# FourRotor2_0.net
KiCad netlist of a schematic drawn in Altium Designer
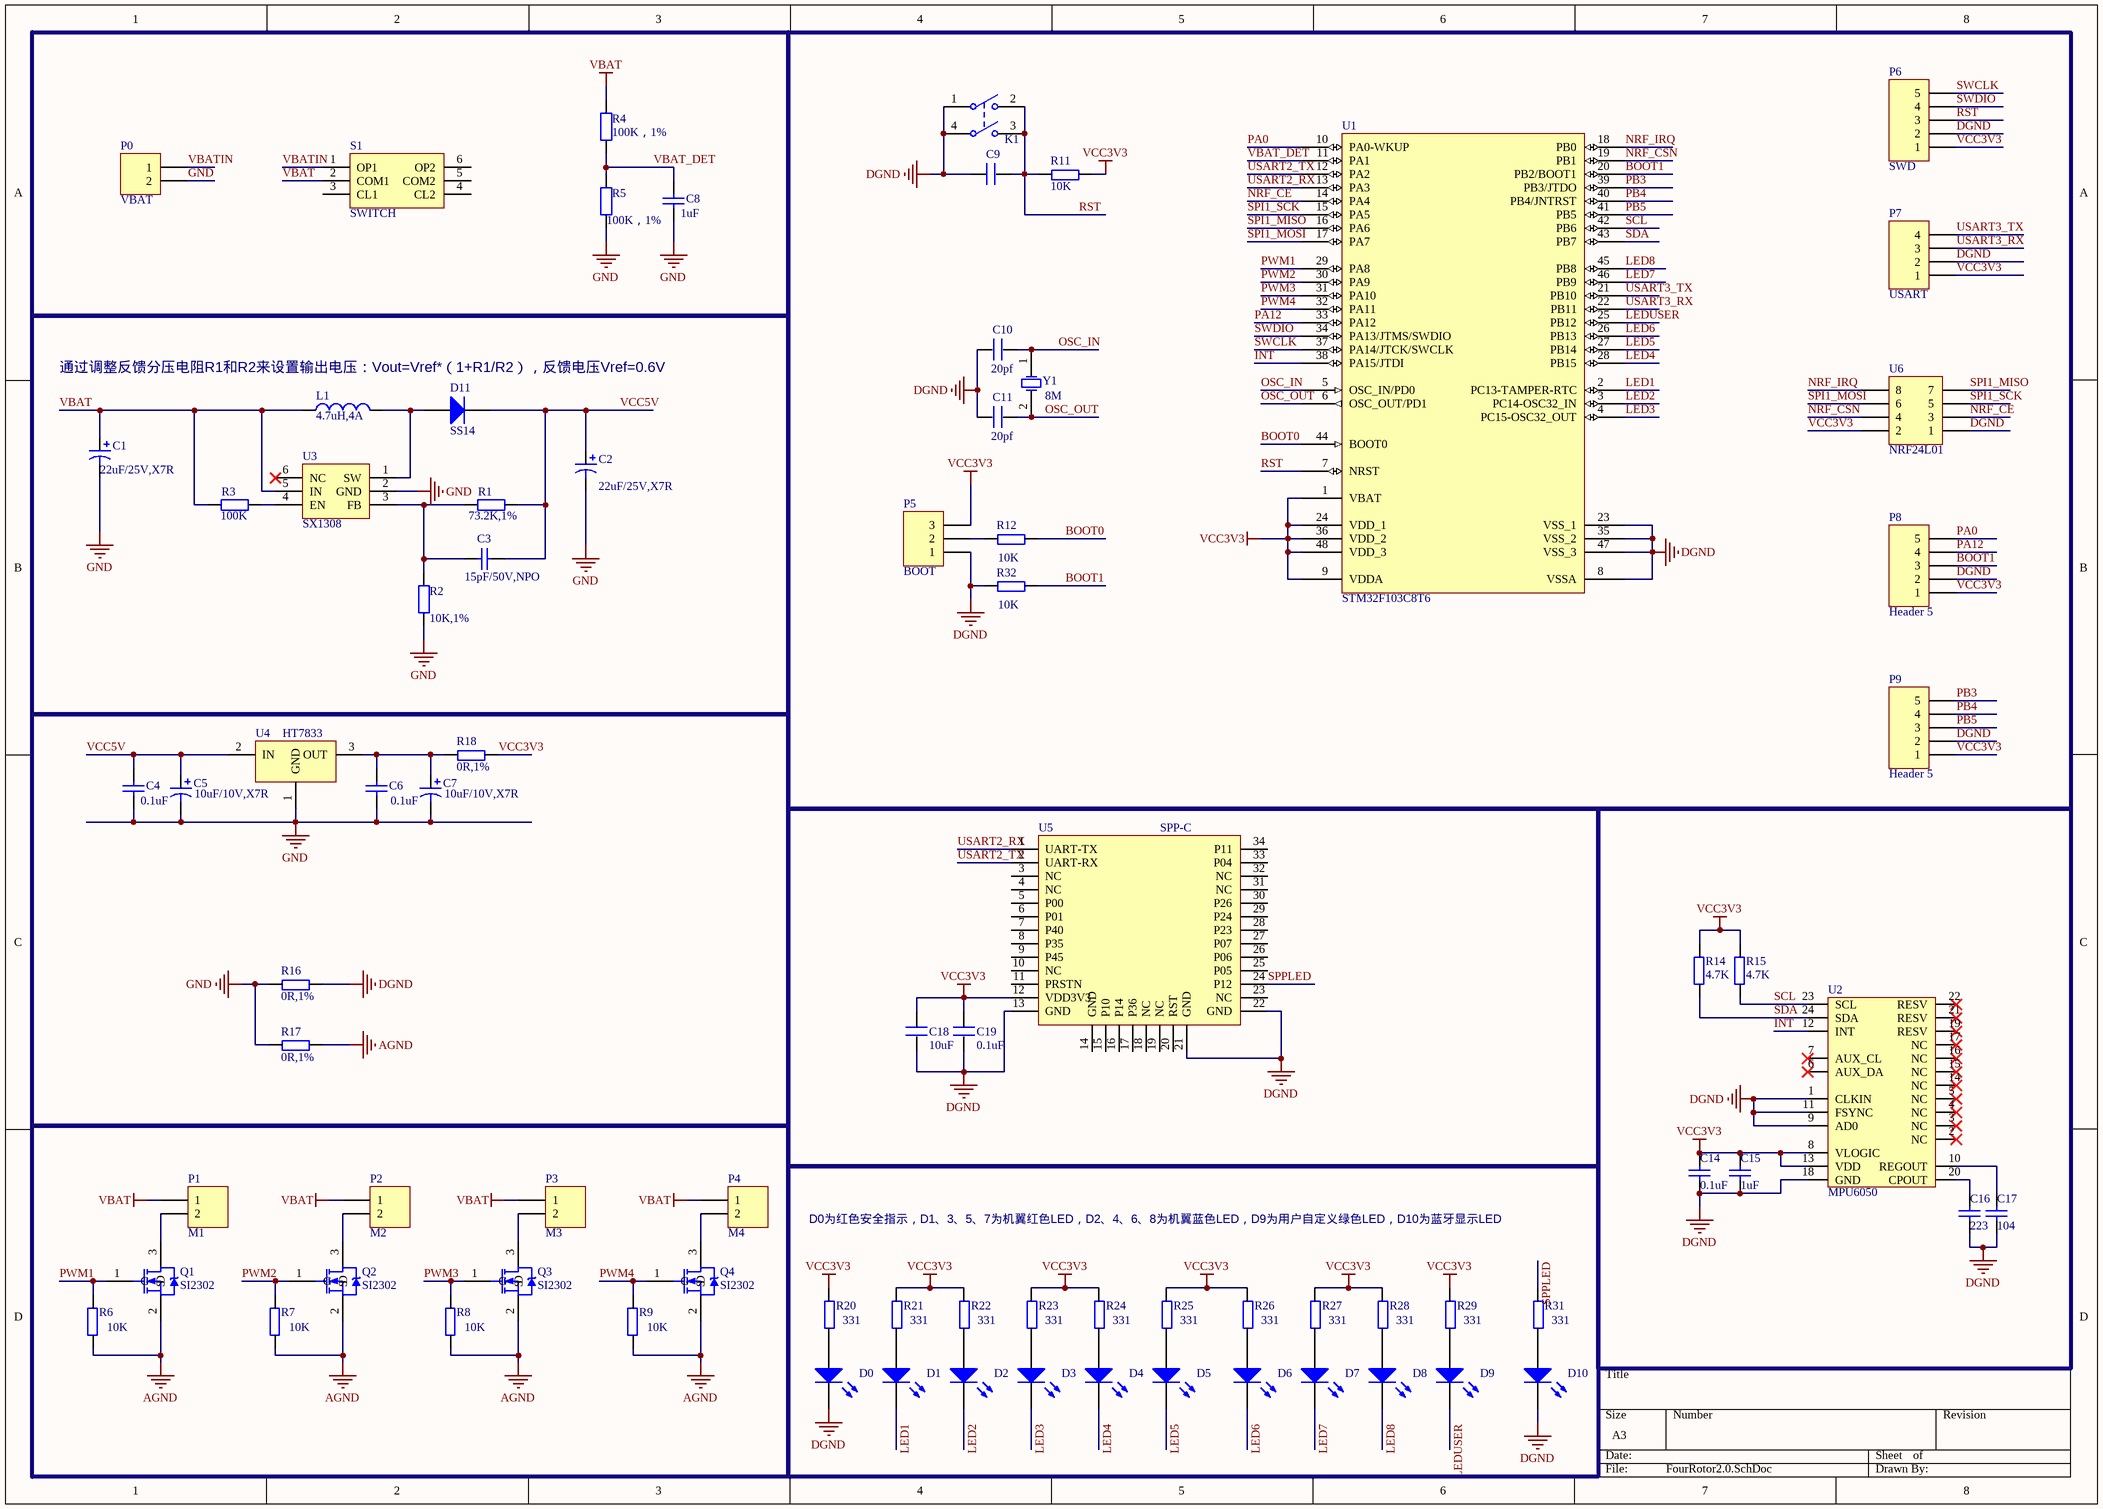
[diagram p0: FourRotor2.0.SchDoc]

(export (version "E")
  (design (tool "Eeschema 10.0.6"))
  (components
    (comp (ref "C1")
      (value "22uF/25V,X7R")
      (footprint "LC-1206_C")
      (description "Polarized Capacitor (Radial)")
      (fields (field (name "Comment") "Cap Pol1") (field (name "PUBLISHER") "Altium Limited"))
      (libsource (lib "Miscellaneous Devices") (part "Cap Pol1"))
    )
    (comp (ref "C2")
      (value "22uF/25V,X7R")
      (footprint "LC-1206_C")
      (description "Polarized Capacitor (Radial)")
      (fields (field (name "Comment") "Cap Pol1") (field (name "PUBLISHER") "Altium Limited"))
      (libsource (lib "Miscellaneous Devices") (part "Cap Pol1"))
    )
    (comp (ref "C3")
      (value "15pF/50V,NPO")
      (footprint "LC-0603_C")
      (description "Capacitor")
      (fields (field (name "Comment") "Cap") (field (name "PUBLISHER") "Altium Limited"))
      (libsource (lib "Miscellaneous Devices") (part "Cap"))
    )
    (comp (ref "C4")
      (value "0.1uF")
      (footprint "LC-0603_C")
      (description "Capacitor")
      (fields (field (name "Comment") "Cap") (field (name "PUBLISHER") "Altium Limited"))
      (libsource (lib "Miscellaneous Devices") (part "Cap"))
    )
    (comp (ref "C5")
      (value "10uF/10V,X7R")
      (footprint "LC-1206_C")
      (description "Polarized Capacitor (Radial)")
      (fields (field (name "Comment") "Cap Pol1") (field (name "PUBLISHER") "Altium Limited"))
      (libsource (lib "Miscellaneous Devices") (part "Cap Pol1"))
    )
    (comp (ref "C6")
      (value "0.1uF")
      (footprint "LC-0603_C")
      (description "Capacitor")
      (fields (field (name "Comment") "Cap") (field (name "PUBLISHER") "Altium Limited"))
      (libsource (lib "Miscellaneous Devices") (part "Cap"))
    )
    (comp (ref "C7")
      (value "10uF/10V,X7R")
      (footprint "LC-1206_C")
      (description "Polarized Capacitor (Radial)")
      (fields (field (name "Comment") "Cap Pol1") (field (name "PUBLISHER") "Altium Limited"))
      (libsource (lib "Miscellaneous Devices") (part "Cap Pol1"))
    )
    (comp (ref "C8")
      (value "1uF")
      (footprint "LC-0603_C")
      (description "Capacitor")
      (fields (field (name "Comment") "Cap") (field (name "PUBLISHER") "Altium Limited"))
      (libsource (lib "Miscellaneous Devices") (part "Cap"))
    )
    (comp (ref "C9")
      (value "1uF")
      (footprint "LC-0603_C")
      (libsource (lib "Explorer STM32F407封装库") (part "C_1"))
    )
    (comp (ref "C10")
      (value "20pf")
      (footprint "LC-0603_C")
      (libsource (lib "Explorer STM32F407封装库") (part "C"))
    )
    (comp (ref "C11")
      (value "20pf")
      (footprint "LC-0603_C")
      (libsource (lib "Explorer STM32F407封装库") (part "C"))
    )
    (comp (ref "C14")
      (value "0.1uF")
      (footprint "LC-0603_C")
      (description "Capacitor")
      (fields (field (name "PUBLISHER") "Altium Limited"))
      (libsource (lib "Miscellaneous Devices") (part "Cap"))
    )
    (comp (ref "C15")
      (value "1uF")
      (footprint "LC-0603_C")
      (description "Capacitor")
      (fields (field (name "PUBLISHER") "Altium Limited"))
      (libsource (lib "Miscellaneous Devices") (part "Cap"))
    )
    (comp (ref "C16")
      (value "223")
      (footprint "LC-0603_C")
      (description "Capacitor")
      (fields (field (name "PUBLISHER") "Altium Limited"))
      (libsource (lib "Miscellaneous Devices") (part "Cap"))
    )
    (comp (ref "C17")
      (value "104")
      (footprint "LC-0603_C")
      (description "Capacitor")
      (fields (field (name "PUBLISHER") "Altium Limited"))
      (libsource (lib "Miscellaneous Devices") (part "Cap"))
    )
    (comp (ref "C18")
      (value "10uF")
      (footprint "LC-0805_C")
      (libsource (lib "Explorer STM32F407封装库") (part "C"))
    )
    (comp (ref "C19")
      (value "0.1uF")
      (footprint "LC-0603_C")
      (libsource (lib "Explorer STM32F407封装库") (part "C"))
    )
    (comp (ref "D0")
      (value "LED0")
      (footprint "LC-0805_LED_S1")
      (description "Typical INFRARED GaAs LED")
      (fields (field (name "PUBLISHER") "Altium Limited"))
      (libsource (lib "Miscellaneous Devices") (part "LED0"))
    )
    (comp (ref "D1")
      (value "LED0")
      (footprint "LC-0805_LED_S1")
      (description "Typical INFRARED GaAs LED")
      (fields (field (name "PUBLISHER") "Altium Limited"))
      (libsource (lib "Miscellaneous Devices") (part "LED0"))
    )
    (comp (ref "D2")
      (value "LED0")
      (footprint "LC-0805_LED_S1")
      (description "Typical INFRARED GaAs LED")
      (fields (field (name "PUBLISHER") "Altium Limited"))
      (libsource (lib "Miscellaneous Devices") (part "LED0"))
    )
    (comp (ref "D3")
      (value "LED0")
      (footprint "LC-0805_LED_S1")
      (description "Typical INFRARED GaAs LED")
      (fields (field (name "PUBLISHER") "Altium Limited"))
      (libsource (lib "Miscellaneous Devices") (part "LED0"))
    )
    (comp (ref "D4")
      (value "LED0")
      (footprint "LC-0805_LED_S1")
      (description "Typical INFRARED GaAs LED")
      (fields (field (name "PUBLISHER") "Altium Limited"))
      (libsource (lib "Miscellaneous Devices") (part "LED0"))
    )
    (comp (ref "D5")
      (value "LED0")
      (footprint "LC-0805_LED_S1")
      (description "Typical INFRARED GaAs LED")
      (fields (field (name "PUBLISHER") "Altium Limited"))
      (libsource (lib "Miscellaneous Devices") (part "LED0"))
    )
    (comp (ref "D6")
      (value "LED0")
      (footprint "LC-0805_LED_S1")
      (description "Typical INFRARED GaAs LED")
      (fields (field (name "PUBLISHER") "Altium Limited"))
      (libsource (lib "Miscellaneous Devices") (part "LED0"))
    )
    (comp (ref "D7")
      (value "LED0")
      (footprint "LC-0805_LED_S1")
      (description "Typical INFRARED GaAs LED")
      (fields (field (name "PUBLISHER") "Altium Limited"))
      (libsource (lib "Miscellaneous Devices") (part "LED0"))
    )
    (comp (ref "D8")
      (value "LED0")
      (footprint "LC-0805_LED_S1")
      (description "Typical INFRARED GaAs LED")
      (fields (field (name "PUBLISHER") "Altium Limited"))
      (libsource (lib "Miscellaneous Devices") (part "LED0"))
    )
    (comp (ref "D9")
      (value "LED0")
      (footprint "LC-0805_LED_S1")
      (description "Typical INFRARED GaAs LED")
      (fields (field (name "PUBLISHER") "Altium Limited"))
      (libsource (lib "Miscellaneous Devices") (part "LED0"))
    )
    (comp (ref "D10")
      (value "LED0")
      (footprint "LC-0805_LED_S1")
      (description "Typical INFRARED GaAs LED")
      (fields (field (name "PUBLISHER") "Altium Limited"))
      (libsource (lib "Miscellaneous Devices") (part "LED0"))
    )
    (comp (ref "D11")
      (value "SS14")
      (footprint "LC-DO-214AC")
      (description "1 Amp General Purpose Rectifier")
      (fields (field (name "PUBLISHER") "Altium Limited"))
      (libsource (lib "Miscellaneous Devices") (part "Diode 1N4001"))
    )
    (comp (ref "K1")
      (value "SW-DPST")
      (footprint "SWITCH2")
      (description "Double-Pole, Single-Throw Switch")
      (fields (field (name "PUBLISHER") "Altium Limited"))
      (libsource (lib "Miscellaneous Devices") (part "SW-DPST"))
    )
    (comp (ref "L1")
      (value "4.7uH,4A")
      (footprint "LC-1812_L")
      (description "Inductor")
      (fields (field (name "PUBLISHER") "Altium Limited"))
      (libsource (lib "Miscellaneous Devices") (part "Inductor"))
    )
    (comp (ref "P0")
      (value "VBAT")
      (footprint "HDR1X2")
      (description "Header, 2-Pin")
      (fields (field (name "PUBLISHER") "Altium Limited"))
      (libsource (lib "") (part "Header 2_1"))
    )
    (comp (ref "P1")
      (value "M1")
      (footprint "HDR1X2")
      (description "Header, 2-Pin")
      (fields (field (name "PUBLISHER") "Altium Limited"))
      (libsource (lib "Miscellaneous Connectors") (part "Header 2"))
    )
    (comp (ref "P2")
      (value "M2")
      (footprint "HDR1X2")
      (description "Header, 2-Pin")
      (fields (field (name "PUBLISHER") "Altium Limited"))
      (libsource (lib "Miscellaneous Connectors") (part "Header 2"))
    )
    (comp (ref "P3")
      (value "M3")
      (footprint "HDR1X2")
      (description "Header, 2-Pin")
      (fields (field (name "PUBLISHER") "Altium Limited"))
      (libsource (lib "Miscellaneous Connectors") (part "Header 2"))
    )
    (comp (ref "P4")
      (value "M4")
      (footprint "HDR1X2")
      (description "Header, 2-Pin")
      (fields (field (name "PUBLISHER") "Altium Limited"))
      (libsource (lib "Miscellaneous Connectors") (part "Header 2"))
    )
    (comp (ref "P5")
      (value "BOOT")
      (footprint "HDR1X3")
      (description "Header, 3-Pin")
      (fields (field (name "PUBLISHER") "Altium Limited"))
      (libsource (lib "Miscellaneous Connectors") (part "Header 3"))
    )
    (comp (ref "P6")
      (value "SWD")
      (footprint "HDR1X5")
      (description "Header, 5-Pin")
      (fields (field (name "PUBLISHER") "Altium Limited"))
      (libsource (lib "Miscellaneous Connectors") (part "Header 5"))
    )
    (comp (ref "P7")
      (value "USART")
      (footprint "HDR1X4")
      (description "Header, 4-Pin")
      (fields (field (name "PUBLISHER") "Altium Limited"))
      (libsource (lib "Miscellaneous Connectors") (part "Header 4"))
    )
    (comp (ref "P8")
      (value "Header 5")
      (footprint "HDR1X5")
      (description "Header, 5-Pin")
      (fields (field (name "PUBLISHER") "Altium Limited"))
      (libsource (lib "Miscellaneous Connectors") (part "Header 5"))
    )
    (comp (ref "P9")
      (value "Header 5")
      (footprint "HDR1X5")
      (description "Header, 5-Pin")
      (fields (field (name "PUBLISHER") "Altium Limited"))
      (libsource (lib "Miscellaneous Connectors") (part "Header 5"))
    )
    (comp (ref "Q1")
      (value "SI2302")
      (footprint "LC-SOT-23(SOT-23-3)")
      (description "N-Channel Power MOSFET")
      (fields (field (name "PUBLISHER") "Altium Limited"))
      (libsource (lib "Miscellaneous Devices") (part "NMOS-2"))
    )
    (comp (ref "Q2")
      (value "SI2302")
      (footprint "LC-SOT-23(SOT-23-3)")
      (description "N-Channel Power MOSFET")
      (fields (field (name "PUBLISHER") "Altium Limited"))
      (libsource (lib "Miscellaneous Devices") (part "NMOS-2"))
    )
    (comp (ref "Q3")
      (value "SI2302")
      (footprint "LC-SOT-23(SOT-23-3)")
      (description "N-Channel Power MOSFET")
      (fields (field (name "PUBLISHER") "Altium Limited"))
      (libsource (lib "Miscellaneous Devices") (part "NMOS-2"))
    )
    (comp (ref "Q4")
      (value "SI2302")
      (footprint "LC-SOT-23(SOT-23-3)")
      (description "N-Channel Power MOSFET")
      (fields (field (name "PUBLISHER") "Altium Limited"))
      (libsource (lib "Miscellaneous Devices") (part "NMOS-2"))
    )
    (comp (ref "R1")
      (value "73.2K,1%")
      (footprint "LC-0603_R")
      (description "Resistor")
      (fields (field (name "Comment") "Res2") (field (name "PUBLISHER") "Altium Limited"))
      (libsource (lib "") (part "Res2_1"))
    )
    (comp (ref "R2")
      (value "10K,1%")
      (footprint "LC-0603_R")
      (description "Resistor")
      (fields (field (name "Comment") "Res2") (field (name "PUBLISHER") "Altium Limited"))
      (libsource (lib "Miscellaneous Devices") (part "Res2"))
    )
    (comp (ref "R3")
      (value "100K")
      (footprint "LC-0603_R")
      (description "Resistor")
      (fields (field (name "Comment") "Res2") (field (name "PUBLISHER") "Altium Limited"))
      (libsource (lib "") (part "Res2_1"))
    )
    (comp (ref "R4")
      (value "100K，1%")
      (footprint "LC-0603_R")
      (description "Resistor")
      (fields (field (name "Comment") "Res2") (field (name "PUBLISHER") "Altium Limited"))
      (libsource (lib "Miscellaneous Devices") (part "Res2"))
    )
    (comp (ref "R5")
      (value "100K，1%")
      (footprint "LC-0603_R")
      (description "Resistor")
      (fields (field (name "Comment") "Res2") (field (name "PUBLISHER") "Altium Limited"))
      (libsource (lib "Miscellaneous Devices") (part "Res2"))
    )
    (comp (ref "R6")
      (value "10K")
      (footprint "LC-0603_R")
      (libsource (lib "Explorer STM32F407封装库") (part "R"))
    )
    (comp (ref "R7")
      (value "10K")
      (footprint "LC-0603_R")
      (libsource (lib "Explorer STM32F407封装库") (part "R"))
    )
    (comp (ref "R8")
      (value "10K")
      (footprint "LC-0603_R")
      (libsource (lib "Explorer STM32F407封装库") (part "R"))
    )
    (comp (ref "R9")
      (value "10K")
      (footprint "LC-0603_R")
      (libsource (lib "Explorer STM32F407封装库") (part "R"))
    )
    (comp (ref "R11")
      (value "10K")
      (footprint "LC-0603_R")
      (libsource (lib "Explorer STM32F407封装库") (part "R_1"))
    )
    (comp (ref "R12")
      (value "10K")
      (footprint "LC-0603_R")
      (libsource (lib "Explorer STM32F407封装库") (part "R"))
    )
    (comp (ref "R14")
      (value "4.7K")
      (footprint "LC-0603_R")
      (libsource (lib "Explorer STM32F407封装库") (part "R_1"))
    )
    (comp (ref "R15")
      (value "4.7K")
      (footprint "LC-0603_R")
      (libsource (lib "Explorer STM32F407封装库") (part "R_1"))
    )
    (comp (ref "R16")
      (value "0R,1%")
      (footprint "LC-0805_R")
      (libsource (lib "Explorer STM32F407封装库") (part "R"))
    )
    (comp (ref "R17")
      (value "0R,1%")
      (footprint "LC-0805_R")
      (libsource (lib "Explorer STM32F407封装库") (part "R"))
    )
    (comp (ref "R18")
      (value "0R,1%")
      (footprint "LC-0805_R")
      (libsource (lib "Explorer STM32F407封装库") (part "R"))
    )
    (comp (ref "R20")
      (value "331")
      (footprint "LC-0603_R")
      (libsource (lib "Explorer STM32F407封装库") (part "R_1"))
    )
    (comp (ref "R21")
      (value "331")
      (footprint "LC-0603_R")
      (libsource (lib "Explorer STM32F407封装库") (part "R_1"))
    )
    (comp (ref "R22")
      (value "331")
      (footprint "LC-0603_R")
      (libsource (lib "Explorer STM32F407封装库") (part "R_1"))
    )
    (comp (ref "R23")
      (value "331")
      (footprint "LC-0603_R")
      (libsource (lib "Explorer STM32F407封装库") (part "R_1"))
    )
    (comp (ref "R24")
      (value "331")
      (footprint "LC-0603_R")
      (libsource (lib "Explorer STM32F407封装库") (part "R_1"))
    )
    (comp (ref "R25")
      (value "331")
      (footprint "LC-0603_R")
      (libsource (lib "Explorer STM32F407封装库") (part "R_1"))
    )
    (comp (ref "R26")
      (value "331")
      (footprint "LC-0603_R")
      (libsource (lib "Explorer STM32F407封装库") (part "R_1"))
    )
    (comp (ref "R27")
      (value "331")
      (footprint "LC-0603_R")
      (libsource (lib "Explorer STM32F407封装库") (part "R_1"))
    )
    (comp (ref "R28")
      (value "331")
      (footprint "LC-0603_R")
      (libsource (lib "Explorer STM32F407封装库") (part "R_1"))
    )
    (comp (ref "R29")
      (value "331")
      (footprint "LC-0603_R")
      (libsource (lib "Explorer STM32F407封装库") (part "R_1"))
    )
    (comp (ref "R31")
      (value "331")
      (footprint "LC-0603_R")
      (libsource (lib "Explorer STM32F407封装库") (part "R_1"))
    )
    (comp (ref "R32")
      (value "10K")
      (footprint "LC-0603_R")
      (libsource (lib "Explorer STM32F407封装库") (part "R"))
    )
    (comp (ref "S1") (value "SWITCH") (footprint "SWITCH_6") (libsource (lib "mzwlib") (part "SWITCH")))
    (comp (ref "U1")
      (value "STM32F103C8T6")
      (footprint "LC-LQFP-48_7x7x05P")
      (description "STM32 ARM-based 32-bit MCU with 64 Kbytes Flash, 48-pin LQFP, Industrial Temperature")
      (fields (field (name "PUBLISHER") "Altium Limited"))
      (libsource (lib "ST Microcontroller 32-Bit STM32") (part "STM32F103C8T6"))
    )
    (comp (ref "U2")
      (value "MPU6050")
      (footprint "LC-QFN-24_4x4x05P")
      (description "9轴运动处理传感器")
      (libsource (lib "Explorer STM32F407封装库") (part "MPU6050"))
    )
    (comp (ref "U3") (value "SX1308") (footprint "LC-SOT-23-6") (libsource (lib "mzwlib") (part "SX1308")))
    (comp (ref "U4")
      (value "HT7833")
      (footprint "LC-SOT-89(SOT-89-3)")
      (libsource (lib "mzwlib") (part "HT7833"))
    )
    (comp (ref "U5") (value "SPP-C") (footprint "SPP-C") (libsource (lib "mzwlib") (part "SPP-C")))
    (comp (ref "U6")
      (value "NRF24L01")
      (footprint "LC-HDR2X4H")
      (description "Header, 4-Pin, Dual row, Right Angle")
      (fields (field (name "PUBLISHER") "Altium Limited"))
      (libsource (lib "Miscellaneous Connectors") (part "Header 4X2H"))
    )
    (comp (ref "Y1")
      (value "~")
      (footprint "LC-HC-49S")
      (description "Crystal Oscillator")
      (fields (field (name "ALTIUM_UNNAMED_1") "8M") (field (name "PUBLISHER") "Altium Limited"))
      (libsource (lib "Explorer STM32F407封装库") (part "XTAL"))
    )
  )
  (nets
    (net (code "1") (name "/BOOT0") (class "Default")
      (node (ref "R12") (pin "2") (pintype "passive"))
      (node (ref "U1") (pin "44") (pinfunction "BOOT0_44") (pintype "input"))
    )
    (net (code "2") (name "/BOOT1") (class "Default")
      (node (ref "P8") (pin "3") (pinfunction "3_3") (pintype "passive"))
      (node (ref "R32") (pin "2") (pintype "passive"))
      (node (ref "U1") (pin "20") (pinfunction "PB2/BOOT1_20") (pintype "bidirectional"))
    )
    (net (code "3") (name "/INT") (class "Default")
      (node (ref "U1") (pin "38") (pinfunction "PA15/JTDI_38") (pintype "bidirectional"))
      (node (ref "U2") (pin "12") (pinfunction "INT_12") (pintype "passive"))
    )
    (net (code "4") (name "/LED1") (class "Default")
      (node (ref "D1") (pin "2") (pinfunction "K_2") (pintype "passive"))
      (node (ref "U1") (pin "2") (pinfunction "PC13-TAMPER-RTC_2") (pintype "bidirectional"))
    )
    (net (code "5") (name "/LED2") (class "Default")
      (node (ref "D2") (pin "2") (pinfunction "K_2") (pintype "passive"))
      (node (ref "U1") (pin "3") (pinfunction "PC14-OSC32_IN_3") (pintype "bidirectional"))
    )
    (net (code "6") (name "/LED3") (class "Default")
      (node (ref "D3") (pin "2") (pinfunction "K_2") (pintype "passive"))
      (node (ref "U1") (pin "4") (pinfunction "PC15-OSC32_OUT_4") (pintype "bidirectional"))
    )
    (net (code "7") (name "/LED4") (class "Default")
      (node (ref "D4") (pin "2") (pinfunction "K_2") (pintype "passive"))
      (node (ref "U1") (pin "28") (pinfunction "PB15_28") (pintype "bidirectional"))
    )
    (net (code "8") (name "/LED5") (class "Default")
      (node (ref "D5") (pin "2") (pinfunction "K_2") (pintype "passive"))
      (node (ref "U1") (pin "27") (pinfunction "PB14_27") (pintype "bidirectional"))
    )
    (net (code "9") (name "/LED6") (class "Default")
      (node (ref "D6") (pin "2") (pinfunction "K_2") (pintype "passive"))
      (node (ref "U1") (pin "26") (pinfunction "PB13_26") (pintype "bidirectional"))
    )
    (net (code "10") (name "/LED7") (class "Default")
      (node (ref "D7") (pin "2") (pinfunction "K_2") (pintype "passive"))
      (node (ref "U1") (pin "46") (pinfunction "PB9_46") (pintype "bidirectional"))
    )
    (net (code "11") (name "/LED8") (class "Default")
      (node (ref "D8") (pin "2") (pinfunction "K_2") (pintype "passive"))
      (node (ref "U1") (pin "45") (pinfunction "PB8_45") (pintype "bidirectional"))
    )
    (net (code "12") (name "/LEDUSER") (class "Default")
      (node (ref "D9") (pin "2") (pinfunction "K_2") (pintype "passive"))
      (node (ref "U1") (pin "25") (pinfunction "PB12_25") (pintype "bidirectional"))
    )
    (net (code "13") (name "/NRF_CE") (class "Default")
      (node (ref "U1") (pin "14") (pinfunction "PA4_14") (pintype "bidirectional"))
      (node (ref "U6") (pin "3") (pinfunction "3_3") (pintype "passive"))
    )
    (net (code "14") (name "/NRF_CSN") (class "Default")
      (node (ref "U1") (pin "19") (pinfunction "PB1_19") (pintype "bidirectional"))
      (node (ref "U6") (pin "4") (pinfunction "4_4") (pintype "passive"))
    )
    (net (code "15") (name "/NRF_IRQ") (class "Default")
      (node (ref "U1") (pin "18") (pinfunction "PB0_18") (pintype "bidirectional"))
      (node (ref "U6") (pin "8") (pinfunction "8_8") (pintype "passive"))
    )
    (net (code "16") (name "/OSC_IN") (class "Default")
      (node (ref "C10") (pin "2") (pintype "passive"))
      (node (ref "U1") (pin "5") (pinfunction "OSC_IN/PD0_5") (pintype "input"))
      (node (ref "Y1") (pin "1") (pinfunction "OSC1_1") (pintype "passive"))
    )
    (net (code "17") (name "/OSC_OUT") (class "Default")
      (node (ref "C11") (pin "2") (pintype "passive"))
      (node (ref "U1") (pin "6") (pinfunction "OSC_OUT/PD1_6") (pintype "output"))
      (node (ref "Y1") (pin "2") (pinfunction "OSC2_2") (pintype "passive"))
    )
    (net (code "18") (name "/PA0") (class "Default")
      (node (ref "P8") (pin "5") (pinfunction "5_5") (pintype "passive"))
      (node (ref "U1") (pin "10") (pinfunction "PA0-WKUP_10") (pintype "bidirectional"))
    )
    (net (code "19") (name "/PA12") (class "Default")
      (node (ref "P8") (pin "4") (pinfunction "4_4") (pintype "passive"))
      (node (ref "U1") (pin "33") (pinfunction "PA12_33") (pintype "bidirectional"))
    )
    (net (code "20") (name "/PB3") (class "Default")
      (node (ref "P9") (pin "5") (pinfunction "5_5") (pintype "passive"))
      (node (ref "U1") (pin "39") (pinfunction "PB3/JTDO_39") (pintype "bidirectional"))
    )
    (net (code "21") (name "/PB4") (class "Default")
      (node (ref "P9") (pin "4") (pinfunction "4_4") (pintype "passive"))
      (node (ref "U1") (pin "40") (pinfunction "PB4/JNTRST_40") (pintype "bidirectional"))
    )
    (net (code "22") (name "/PB5") (class "Default")
      (node (ref "P9") (pin "3") (pinfunction "3_3") (pintype "passive"))
      (node (ref "U1") (pin "41") (pinfunction "PB5_41") (pintype "bidirectional"))
    )
    (net (code "23") (name "/PWM1") (class "Default")
      (node (ref "Q1") (pin "1") (pinfunction "G_1") (pintype "passive"))
      (node (ref "R6") (pin "1") (pintype "passive"))
      (node (ref "U1") (pin "29") (pinfunction "PA8_29") (pintype "bidirectional"))
    )
    (net (code "24") (name "/PWM2") (class "Default")
      (node (ref "Q2") (pin "1") (pinfunction "G_1") (pintype "passive"))
      (node (ref "R7") (pin "1") (pintype "passive"))
      (node (ref "U1") (pin "30") (pinfunction "PA9_30") (pintype "bidirectional"))
    )
    (net (code "25") (name "/PWM3") (class "Default")
      (node (ref "Q3") (pin "1") (pinfunction "G_1") (pintype "passive"))
      (node (ref "R8") (pin "1") (pintype "passive"))
      (node (ref "U1") (pin "31") (pinfunction "PA10_31") (pintype "bidirectional"))
    )
    (net (code "26") (name "/PWM4") (class "Default")
      (node (ref "Q4") (pin "1") (pinfunction "G_1") (pintype "passive"))
      (node (ref "R9") (pin "1") (pintype "passive"))
      (node (ref "U1") (pin "32") (pinfunction "PA11_32") (pintype "bidirectional"))
    )
    (net (code "27") (name "/RST") (class "Default")
      (node (ref "C9") (pin "2") (pintype "passive"))
      (node (ref "K1") (pin "2") (pinfunction "NO1_2") (pintype "passive"))
      (node (ref "K1") (pin "3") (pinfunction "NO2_3") (pintype "passive"))
      (node (ref "P6") (pin "3") (pinfunction "3_3") (pintype "passive"))
      (node (ref "R11") (pin "1") (pintype "passive"))
      (node (ref "U1") (pin "7") (pinfunction "NRST_7") (pintype "bidirectional"))
    )
    (net (code "28") (name "/SCL") (class "Default")
      (node (ref "R15") (pin "2") (pintype "passive"))
      (node (ref "U1") (pin "42") (pinfunction "PB6_42") (pintype "bidirectional"))
      (node (ref "U2") (pin "23") (pinfunction "SCL_23") (pintype "passive"))
    )
    (net (code "29") (name "/SDA") (class "Default")
      (node (ref "R14") (pin "2") (pintype "passive"))
      (node (ref "U1") (pin "43") (pinfunction "PB7_43") (pintype "bidirectional"))
      (node (ref "U2") (pin "24") (pinfunction "SDA_24") (pintype "passive"))
    )
    (net (code "30") (name "/SPI1_MISO") (class "Default")
      (node (ref "U1") (pin "16") (pinfunction "PA6_16") (pintype "bidirectional"))
      (node (ref "U6") (pin "7") (pinfunction "7_7") (pintype "passive"))
    )
    (net (code "31") (name "/SPI1_MOSI") (class "Default")
      (node (ref "U1") (pin "17") (pinfunction "PA7_17") (pintype "bidirectional"))
      (node (ref "U6") (pin "6") (pinfunction "6_6") (pintype "passive"))
    )
    (net (code "32") (name "/SPI1_SCK") (class "Default")
      (node (ref "U1") (pin "15") (pinfunction "PA5_15") (pintype "bidirectional"))
      (node (ref "U6") (pin "5") (pinfunction "5_5") (pintype "passive"))
    )
    (net (code "33") (name "/SPPLED") (class "Default")
      (node (ref "R31") (pin "2") (pintype "passive"))
      (node (ref "U5") (pin "24") (pinfunction "P12_24") (pintype "passive"))
    )
    (net (code "34") (name "/SWCLK") (class "Default")
      (node (ref "P6") (pin "5") (pinfunction "5_5") (pintype "passive"))
      (node (ref "U1") (pin "37") (pinfunction "PA14/JTCK/SWCLK_37") (pintype "bidirectional"))
    )
    (net (code "35") (name "/SWDIO") (class "Default")
      (node (ref "P6") (pin "4") (pinfunction "4_4") (pintype "passive"))
      (node (ref "U1") (pin "34") (pinfunction "PA13/JTMS/SWDIO_34") (pintype "bidirectional"))
    )
    (net (code "36") (name "/USART2_RX") (class "Default")
      (node (ref "U1") (pin "13") (pinfunction "PA3_13") (pintype "bidirectional"))
      (node (ref "U5") (pin "1") (pinfunction "UART-TX_1") (pintype "passive"))
    )
    (net (code "37") (name "/USART2_TX") (class "Default")
      (node (ref "U1") (pin "12") (pinfunction "PA2_12") (pintype "bidirectional"))
      (node (ref "U5") (pin "2") (pinfunction "UART-RX_2") (pintype "passive"))
    )
    (net (code "38") (name "/USART3_RX") (class "Default")
      (node (ref "P7") (pin "3") (pinfunction "3_3") (pintype "passive"))
      (node (ref "U1") (pin "22") (pinfunction "PB11_22") (pintype "bidirectional"))
    )
    (net (code "39") (name "/USART3_TX") (class "Default")
      (node (ref "P7") (pin "4") (pinfunction "4_4") (pintype "passive"))
      (node (ref "U1") (pin "21") (pinfunction "PB10_21") (pintype "bidirectional"))
    )
    (net (code "40") (name "/VBATIN") (class "Default")
      (node (ref "P0") (pin "1") (pinfunction "1_1") (pintype "passive"))
      (node (ref "S1") (pin "1") (pinfunction "OP1_1") (pintype "passive"))
    )
    (net (code "41") (name "/VBAT_DET") (class "Default")
      (node (ref "C8") (pin "2") (pinfunction "2_2") (pintype "passive"))
      (node (ref "R4") (pin "1") (pinfunction "1_1") (pintype "passive"))
      (node (ref "R5") (pin "2") (pinfunction "2_2") (pintype "passive"))
      (node (ref "U1") (pin "11") (pinfunction "PA1_11") (pintype "bidirectional"))
    )
    (net (code "42") (name "/VCC5V") (class "Default")
      (node (ref "C2") (pin "1") (pinfunction "1_1") (pintype "passive"))
      (node (ref "C3") (pin "2") (pinfunction "2_2") (pintype "passive"))
      (node (ref "C4") (pin "2") (pinfunction "2_2") (pintype "passive"))
      (node (ref "C5") (pin "1") (pinfunction "1_1") (pintype "passive"))
      (node (ref "D11") (pin "2") (pinfunction "K_2") (pintype "passive"))
      (node (ref "R1") (pin "2") (pinfunction "2_2") (pintype "passive"))
      (node (ref "U4") (pin "2") (pinfunction "IN_2") (pintype "passive"))
    )
    (net (code "43") (name "AGND") (class "Default")
      (node (ref "Q1") (pin "2") (pinfunction "S_2") (pintype "passive"))
      (node (ref "Q2") (pin "2") (pinfunction "S_2") (pintype "passive"))
      (node (ref "Q3") (pin "2") (pinfunction "S_2") (pintype "passive"))
      (node (ref "Q4") (pin "2") (pinfunction "S_2") (pintype "passive"))
      (node (ref "R17") (pin "2") (pintype "passive"))
      (node (ref "R6") (pin "2") (pintype "passive"))
      (node (ref "R7") (pin "2") (pintype "passive"))
      (node (ref "R8") (pin "2") (pintype "passive"))
      (node (ref "R9") (pin "2") (pintype "passive"))
    )
    (net (code "44") (name "DGND") (class "Default")
      (node (ref "C10") (pin "1") (pintype "passive"))
      (node (ref "C11") (pin "1") (pintype "passive"))
      (node (ref "C14") (pin "1") (pinfunction "1_1") (pintype "passive"))
      (node (ref "C15") (pin "1") (pinfunction "1_1") (pintype "passive"))
      (node (ref "C16") (pin "1") (pinfunction "1_1") (pintype "passive"))
      (node (ref "C17") (pin "1") (pinfunction "1_1") (pintype "passive"))
      (node (ref "C18") (pin "1") (pintype "passive"))
      (node (ref "C19") (pin "1") (pintype "passive"))
      (node (ref "C9") (pin "1") (pintype "passive"))
      (node (ref "D0") (pin "2") (pinfunction "K_2") (pintype "passive"))
      (node (ref "D10") (pin "2") (pinfunction "K_2") (pintype "passive"))
      (node (ref "K1") (pin "1") (pinfunction "COMMON1_1") (pintype "passive"))
      (node (ref "K1") (pin "4") (pinfunction "COMMON2_4") (pintype "passive"))
      (node (ref "P5") (pin "1") (pinfunction "1_1") (pintype "passive"))
      (node (ref "P6") (pin "2") (pinfunction "2_2") (pintype "passive"))
      (node (ref "P7") (pin "2") (pinfunction "2_2") (pintype "passive"))
      (node (ref "P8") (pin "2") (pinfunction "2_2") (pintype "passive"))
      (node (ref "P9") (pin "2") (pinfunction "2_2") (pintype "passive"))
      (node (ref "R16") (pin "2") (pintype "passive"))
      (node (ref "R32") (pin "1") (pintype "passive"))
      (node (ref "U1") (pin "23") (pinfunction "VSS_1_23") (pintype "power_in"))
      (node (ref "U1") (pin "35") (pinfunction "VSS_2_35") (pintype "power_in"))
      (node (ref "U1") (pin "47") (pinfunction "VSS_3_47") (pintype "power_in"))
      (node (ref "U1") (pin "8") (pinfunction "VSSA_8") (pintype "power_in"))
      (node (ref "U2") (pin "1") (pinfunction "CLKIN_1") (pintype "passive"))
      (node (ref "U2") (pin "11") (pinfunction "FSYNC_11") (pintype "passive"))
      (node (ref "U2") (pin "18") (pinfunction "GND_18") (pintype "passive"))
      (node (ref "U2") (pin "9") (pinfunction "AD0_9") (pintype "passive"))
      (node (ref "U5") (pin "13") (pinfunction "GND_13") (pintype "passive"))
      (node (ref "U5") (pin "21") (pinfunction "GND_21") (pintype "passive"))
      (node (ref "U5") (pin "22") (pinfunction "GND_22") (pintype "passive"))
      (node (ref "U6") (pin "1") (pinfunction "1_1") (pintype "passive"))
    )
    (net (code "45") (name "GND") (class "Default")
      (node (ref "C1") (pin "2") (pinfunction "2_2") (pintype "passive"))
      (node (ref "C2") (pin "2") (pinfunction "2_2") (pintype "passive"))
      (node (ref "C4") (pin "1") (pinfunction "1_1") (pintype "passive"))
      (node (ref "C5") (pin "2") (pinfunction "2_2") (pintype "passive"))
      (node (ref "C6") (pin "1") (pinfunction "1_1") (pintype "passive"))
      (node (ref "C7") (pin "2") (pinfunction "2_2") (pintype "passive"))
      (node (ref "C8") (pin "1") (pinfunction "1_1") (pintype "passive"))
      (node (ref "P0") (pin "2") (pinfunction "2_2") (pintype "passive"))
      (node (ref "R16") (pin "1") (pintype "passive"))
      (node (ref "R17") (pin "1") (pintype "passive"))
      (node (ref "R2") (pin "1") (pinfunction "1_1") (pintype "passive"))
      (node (ref "R5") (pin "1") (pinfunction "1_1") (pintype "passive"))
      (node (ref "U3") (pin "2") (pinfunction "GND_2") (pintype "passive"))
      (node (ref "U4") (pin "1") (pinfunction "GND_1") (pintype "passive"))
    )
    (net (code "46") (name "Net-(D0-A)") (class "Default")
      (node (ref "D0") (pin "1") (pinfunction "A_1") (pintype "passive"))
      (node (ref "R20") (pin "1") (pintype "passive"))
    )
    (net (code "47") (name "Net-(D1-A)") (class "Default")
      (node (ref "D1") (pin "1") (pinfunction "A_1") (pintype "passive"))
      (node (ref "R21") (pin "1") (pintype "passive"))
    )
    (net (code "48") (name "Net-(D2-A)") (class "Default")
      (node (ref "D2") (pin "1") (pinfunction "A_1") (pintype "passive"))
      (node (ref "R22") (pin "1") (pintype "passive"))
    )
    (net (code "49") (name "Net-(D3-A)") (class "Default")
      (node (ref "D3") (pin "1") (pinfunction "A_1") (pintype "passive"))
      (node (ref "R23") (pin "1") (pintype "passive"))
    )
    (net (code "50") (name "Net-(D4-A)") (class "Default")
      (node (ref "D4") (pin "1") (pinfunction "A_1") (pintype "passive"))
      (node (ref "R24") (pin "1") (pintype "passive"))
    )
    (net (code "51") (name "Net-(D5-A)") (class "Default")
      (node (ref "D5") (pin "1") (pinfunction "A_1") (pintype "passive"))
      (node (ref "R25") (pin "1") (pintype "passive"))
    )
    (net (code "52") (name "Net-(D6-A)") (class "Default")
      (node (ref "D6") (pin "1") (pinfunction "A_1") (pintype "passive"))
      (node (ref "R26") (pin "1") (pintype "passive"))
    )
    (net (code "53") (name "Net-(D7-A)") (class "Default")
      (node (ref "D7") (pin "1") (pinfunction "A_1") (pintype "passive"))
      (node (ref "R27") (pin "1") (pintype "passive"))
    )
    (net (code "54") (name "Net-(D8-A)") (class "Default")
      (node (ref "D8") (pin "1") (pinfunction "A_1") (pintype "passive"))
      (node (ref "R28") (pin "1") (pintype "passive"))
    )
    (net (code "55") (name "Net-(D9-A)") (class "Default")
      (node (ref "D9") (pin "1") (pinfunction "A_1") (pintype "passive"))
      (node (ref "R29") (pin "1") (pintype "passive"))
    )
    (net (code "56") (name "Net-(D10-A)") (class "Default")
      (node (ref "D10") (pin "1") (pinfunction "A_1") (pintype "passive"))
      (node (ref "R31") (pin "1") (pintype "passive"))
    )
    (net (code "57") (name "Net-(D11-A)") (class "Default")
      (node (ref "D11") (pin "1") (pinfunction "A_1") (pintype "passive"))
      (node (ref "L1") (pin "2") (pinfunction "2_2") (pintype "passive"))
      (node (ref "U3") (pin "1") (pinfunction "SW_1") (pintype "passive"))
    )
    (net (code "58") (name "Net-(P5-Pad2)") (class "Default")
      (node (ref "P5") (pin "2") (pinfunction "2_2") (pintype "passive"))
      (node (ref "R12") (pin "1") (pintype "passive"))
    )
    (net (code "59") (name "Net-(Q1-D)") (class "Default")
      (node (ref "P1") (pin "2") (pinfunction "2_2") (pintype "passive"))
      (node (ref "Q1") (pin "3") (pinfunction "D_3") (pintype "passive"))
    )
    (net (code "60") (name "Net-(Q2-D)") (class "Default")
      (node (ref "P2") (pin "2") (pinfunction "2_2") (pintype "passive"))
      (node (ref "Q2") (pin "3") (pinfunction "D_3") (pintype "passive"))
    )
    (net (code "61") (name "Net-(Q3-D)") (class "Default")
      (node (ref "P3") (pin "2") (pinfunction "2_2") (pintype "passive"))
      (node (ref "Q3") (pin "3") (pinfunction "D_3") (pintype "passive"))
    )
    (net (code "62") (name "Net-(Q4-D)") (class "Default")
      (node (ref "P4") (pin "2") (pinfunction "2_2") (pintype "passive"))
      (node (ref "Q4") (pin "3") (pinfunction "D_3") (pintype "passive"))
    )
    (net (code "63") (name "Net-(U2-CPOUT)") (class "Default")
      (node (ref "C16") (pin "2") (pinfunction "2_2") (pintype "passive"))
      (node (ref "U2") (pin "20") (pinfunction "CPOUT_20") (pintype "passive"))
    )
    (net (code "64") (name "Net-(U2-REGOUT)") (class "Default")
      (node (ref "C17") (pin "2") (pinfunction "2_2") (pintype "passive"))
      (node (ref "U2") (pin "10") (pinfunction "REGOUT_10") (pintype "passive"))
    )
    (net (code "65") (name "Net-(U3-EN)") (class "Default")
      (node (ref "R3") (pin "2") (pinfunction "2_2") (pintype "passive"))
      (node (ref "U3") (pin "4") (pinfunction "EN_4") (pintype "passive"))
    )
    (net (code "66") (name "Net-(U3-FB)") (class "Default")
      (node (ref "C3") (pin "1") (pinfunction "1_1") (pintype "passive"))
      (node (ref "R1") (pin "1") (pinfunction "1_1") (pintype "passive"))
      (node (ref "R2") (pin "2") (pinfunction "2_2") (pintype "passive"))
      (node (ref "U3") (pin "3") (pinfunction "FB_3") (pintype "passive"))
    )
    (net (code "67") (name "Net-(U4-OUT)") (class "Default")
      (node (ref "C6") (pin "2") (pinfunction "2_2") (pintype "passive"))
      (node (ref "C7") (pin "1") (pinfunction "1_1") (pintype "passive"))
      (node (ref "R18") (pin "1") (pintype "passive"))
      (node (ref "U4") (pin "3") (pinfunction "OUT_3") (pintype "passive"))
    )
    (net (code "68") (name "VBAT") (class "Default")
      (node (ref "C1") (pin "1") (pinfunction "1_1") (pintype "passive"))
      (node (ref "L1") (pin "1") (pinfunction "1_1") (pintype "passive"))
      (node (ref "P1") (pin "1") (pinfunction "1_1") (pintype "passive"))
      (node (ref "P2") (pin "1") (pinfunction "1_1") (pintype "passive"))
      (node (ref "P3") (pin "1") (pinfunction "1_1") (pintype "passive"))
      (node (ref "P4") (pin "1") (pinfunction "1_1") (pintype "passive"))
      (node (ref "R3") (pin "1") (pinfunction "1_1") (pintype "passive"))
      (node (ref "R4") (pin "2") (pinfunction "2_2") (pintype "passive"))
      (node (ref "S1") (pin "2") (pinfunction "COM1_2") (pintype "passive"))
      (node (ref "U3") (pin "5") (pinfunction "IN_5") (pintype "passive"))
    )
    (net (code "69") (name "VCC3V3") (class "Default")
      (node (ref "C14") (pin "2") (pinfunction "2_2") (pintype "passive"))
      (node (ref "C15") (pin "2") (pinfunction "2_2") (pintype "passive"))
      (node (ref "C18") (pin "2") (pintype "passive"))
      (node (ref "C19") (pin "2") (pintype "passive"))
      (node (ref "P5") (pin "3") (pinfunction "3_3") (pintype "passive"))
      (node (ref "P6") (pin "1") (pinfunction "1_1") (pintype "passive"))
      (node (ref "P7") (pin "1") (pinfunction "1_1") (pintype "passive"))
      (node (ref "P8") (pin "1") (pinfunction "1_1") (pintype "passive"))
      (node (ref "P9") (pin "1") (pinfunction "1_1") (pintype "passive"))
      (node (ref "R11") (pin "2") (pintype "passive"))
      (node (ref "R14") (pin "1") (pintype "passive"))
      (node (ref "R15") (pin "1") (pintype "passive"))
      (node (ref "R18") (pin "2") (pintype "passive"))
      (node (ref "R20") (pin "2") (pintype "passive"))
      (node (ref "R21") (pin "2") (pintype "passive"))
      (node (ref "R22") (pin "2") (pintype "passive"))
      (node (ref "R23") (pin "2") (pintype "passive"))
      (node (ref "R24") (pin "2") (pintype "passive"))
      (node (ref "R25") (pin "2") (pintype "passive"))
      (node (ref "R26") (pin "2") (pintype "passive"))
      (node (ref "R27") (pin "2") (pintype "passive"))
      (node (ref "R28") (pin "2") (pintype "passive"))
      (node (ref "R29") (pin "2") (pintype "passive"))
      (node (ref "U1") (pin "1") (pinfunction "VBAT_1") (pintype "power_in"))
      (node (ref "U1") (pin "24") (pinfunction "VDD_1_24") (pintype "power_in"))
      (node (ref "U1") (pin "36") (pinfunction "VDD_2_36") (pintype "power_in"))
      (node (ref "U1") (pin "48") (pinfunction "VDD_3_48") (pintype "power_in"))
      (node (ref "U1") (pin "9") (pinfunction "VDDA_9") (pintype "power_in"))
      (node (ref "U2") (pin "13") (pinfunction "VDD_13") (pintype "passive"))
      (node (ref "U2") (pin "8") (pinfunction "VLOGIC_8") (pintype "passive"))
      (node (ref "U5") (pin "12") (pinfunction "VDD3V3_12") (pintype "passive"))
      (node (ref "U6") (pin "2") (pinfunction "2_2") (pintype "passive"))
    )
    (net (code "70") (name "unconnected-(S1-CL1-Pad3)") (class "Default")
      (node (ref "S1") (pin "3") (pinfunction "CL1_3") (pintype "passive"))
    )
    (net (code "71") (name "unconnected-(S1-CL2-Pad4)") (class "Default")
      (node (ref "S1") (pin "4") (pinfunction "CL2_4") (pintype "passive"))
    )
    (net (code "72") (name "unconnected-(S1-COM2-Pad5)") (class "Default")
      (node (ref "S1") (pin "5") (pinfunction "COM2_5") (pintype "passive"))
    )
    (net (code "73") (name "unconnected-(S1-OP2-Pad6)") (class "Default")
      (node (ref "S1") (pin "6") (pinfunction "OP2_6") (pintype "passive"))
    )
    (net (code "74") (name "unconnected-(U2-AUX_CL-Pad7)") (class "Default")
      (node (ref "U2") (pin "7") (pinfunction "AUX_CL_7") (pintype "passive+no_connect"))
    )
    (net (code "75") (name "unconnected-(U2-AUX_DA-Pad6)") (class "Default")
      (node (ref "U2") (pin "6") (pinfunction "AUX_DA_6") (pintype "passive+no_connect"))
    )
    (net (code "76") (name "unconnected-(U2-NC-Pad2)") (class "Default")
      (node (ref "U2") (pin "2") (pinfunction "NC_2") (pintype "passive+no_connect"))
    )
    (net (code "77") (name "unconnected-(U2-NC-Pad3)") (class "Default")
      (node (ref "U2") (pin "3") (pinfunction "NC_3") (pintype "passive+no_connect"))
    )
    (net (code "78") (name "unconnected-(U2-NC-Pad4)") (class "Default")
      (node (ref "U2") (pin "4") (pinfunction "NC_4") (pintype "passive+no_connect"))
    )
    (net (code "79") (name "unconnected-(U2-NC-Pad5)") (class "Default")
      (node (ref "U2") (pin "5") (pinfunction "NC_5") (pintype "passive+no_connect"))
    )
    (net (code "80") (name "unconnected-(U2-NC-Pad14)") (class "Default")
      (node (ref "U2") (pin "14") (pinfunction "NC_14") (pintype "passive+no_connect"))
    )
    (net (code "81") (name "unconnected-(U2-NC-Pad15)") (class "Default")
      (node (ref "U2") (pin "15") (pinfunction "NC_15") (pintype "passive+no_connect"))
    )
    (net (code "82") (name "unconnected-(U2-NC-Pad16)") (class "Default")
      (node (ref "U2") (pin "16") (pinfunction "NC_16") (pintype "passive+no_connect"))
    )
    (net (code "83") (name "unconnected-(U2-NC-Pad17)") (class "Default")
      (node (ref "U2") (pin "17") (pinfunction "NC_17") (pintype "passive+no_connect"))
    )
    (net (code "84") (name "unconnected-(U2-RESV-Pad19)") (class "Default")
      (node (ref "U2") (pin "19") (pinfunction "RESV_19") (pintype "passive+no_connect"))
    )
    (net (code "85") (name "unconnected-(U2-RESV-Pad21)") (class "Default")
      (node (ref "U2") (pin "21") (pinfunction "RESV_21") (pintype "passive+no_connect"))
    )
    (net (code "86") (name "unconnected-(U2-RESV-Pad22)") (class "Default")
      (node (ref "U2") (pin "22") (pinfunction "RESV_22") (pintype "passive+no_connect"))
    )
    (net (code "87") (name "unconnected-(U3-NC-Pad6)") (class "Default")
      (node (ref "U3") (pin "6") (pinfunction "NC_6") (pintype "passive+no_connect"))
    )
    (net (code "88") (name "unconnected-(U5-GND-Pad14)") (class "Default")
      (node (ref "U5") (pin "14") (pinfunction "GND_14") (pintype "passive"))
    )
    (net (code "89") (name "unconnected-(U5-NC-Pad3)") (class "Default")
      (node (ref "U5") (pin "3") (pinfunction "NC_3") (pintype "passive"))
    )
    (net (code "90") (name "unconnected-(U5-NC-Pad4)") (class "Default")
      (node (ref "U5") (pin "4") (pinfunction "NC_4") (pintype "passive"))
    )
    (net (code "91") (name "unconnected-(U5-NC-Pad10)") (class "Default")
      (node (ref "U5") (pin "10") (pinfunction "NC_10") (pintype "passive"))
    )
    (net (code "92") (name "unconnected-(U5-NC-Pad18)") (class "Default")
      (node (ref "U5") (pin "18") (pinfunction "NC_18") (pintype "passive"))
    )
    (net (code "93") (name "unconnected-(U5-NC-Pad19)") (class "Default")
      (node (ref "U5") (pin "19") (pinfunction "NC_19") (pintype "passive"))
    )
    (net (code "94") (name "unconnected-(U5-NC-Pad23)") (class "Default")
      (node (ref "U5") (pin "23") (pinfunction "NC_23") (pintype "passive"))
    )
    (net (code "95") (name "unconnected-(U5-NC-Pad31)") (class "Default")
      (node (ref "U5") (pin "31") (pinfunction "NC_31") (pintype "passive"))
    )
    (net (code "96") (name "unconnected-(U5-NC-Pad32)") (class "Default")
      (node (ref "U5") (pin "32") (pinfunction "NC_32") (pintype "passive"))
    )
    (net (code "97") (name "unconnected-(U5-P00-Pad5)") (class "Default")
      (node (ref "U5") (pin "5") (pinfunction "P00_5") (pintype "passive"))
    )
    (net (code "98") (name "unconnected-(U5-P01-Pad6)") (class "Default")
      (node (ref "U5") (pin "6") (pinfunction "P01_6") (pintype "passive"))
    )
    (net (code "99") (name "unconnected-(U5-P04-Pad33)") (class "Default")
      (node (ref "U5") (pin "33") (pinfunction "P04_33") (pintype "passive"))
    )
    (net (code "100") (name "unconnected-(U5-P05-Pad25)") (class "Default")
      (node (ref "U5") (pin "25") (pinfunction "P05_25") (pintype "passive"))
    )
    (net (code "101") (name "unconnected-(U5-P06-Pad26)") (class "Default")
      (node (ref "U5") (pin "26") (pinfunction "P06_26") (pintype "passive"))
    )
    (net (code "102") (name "unconnected-(U5-P07-Pad27)") (class "Default")
      (node (ref "U5") (pin "27") (pinfunction "P07_27") (pintype "passive"))
    )
    (net (code "103") (name "unconnected-(U5-P10-Pad15)") (class "Default")
      (node (ref "U5") (pin "15") (pinfunction "P10_15") (pintype "passive"))
    )
    (net (code "104") (name "unconnected-(U5-P11-Pad34)") (class "Default")
      (node (ref "U5") (pin "34") (pinfunction "P11_34") (pintype "passive"))
    )
    (net (code "105") (name "unconnected-(U5-P14-Pad16)") (class "Default")
      (node (ref "U5") (pin "16") (pinfunction "P14_16") (pintype "passive"))
    )
    (net (code "106") (name "unconnected-(U5-P23-Pad28)") (class "Default")
      (node (ref "U5") (pin "28") (pinfunction "P23_28") (pintype "passive"))
    )
    (net (code "107") (name "unconnected-(U5-P24-Pad29)") (class "Default")
      (node (ref "U5") (pin "29") (pinfunction "P24_29") (pintype "passive"))
    )
    (net (code "108") (name "unconnected-(U5-P26-Pad30)") (class "Default")
      (node (ref "U5") (pin "30") (pinfunction "P26_30") (pintype "passive"))
    )
    (net (code "109") (name "unconnected-(U5-P35-Pad8)") (class "Default")
      (node (ref "U5") (pin "8") (pinfunction "P35_8") (pintype "passive"))
    )
    (net (code "110") (name "unconnected-(U5-P36-Pad17)") (class "Default")
      (node (ref "U5") (pin "17") (pinfunction "P36_17") (pintype "passive"))
    )
    (net (code "111") (name "unconnected-(U5-P40-Pad7)") (class "Default")
      (node (ref "U5") (pin "7") (pinfunction "P40_7") (pintype "passive"))
    )
    (net (code "112") (name "unconnected-(U5-P45-Pad9)") (class "Default")
      (node (ref "U5") (pin "9") (pinfunction "P45_9") (pintype "passive"))
    )
    (net (code "113") (name "unconnected-(U5-PRSTN-Pad11)") (class "Default")
      (node (ref "U5") (pin "11") (pinfunction "PRSTN_11") (pintype "passive"))
    )
    (net (code "114") (name "unconnected-(U5-RST-Pad20)") (class "Default")
      (node (ref "U5") (pin "20") (pinfunction "RST_20") (pintype "passive"))
    )
  )
)
